# teensyShield3.net
KiCad netlist of a schematic drawn in EAGLE
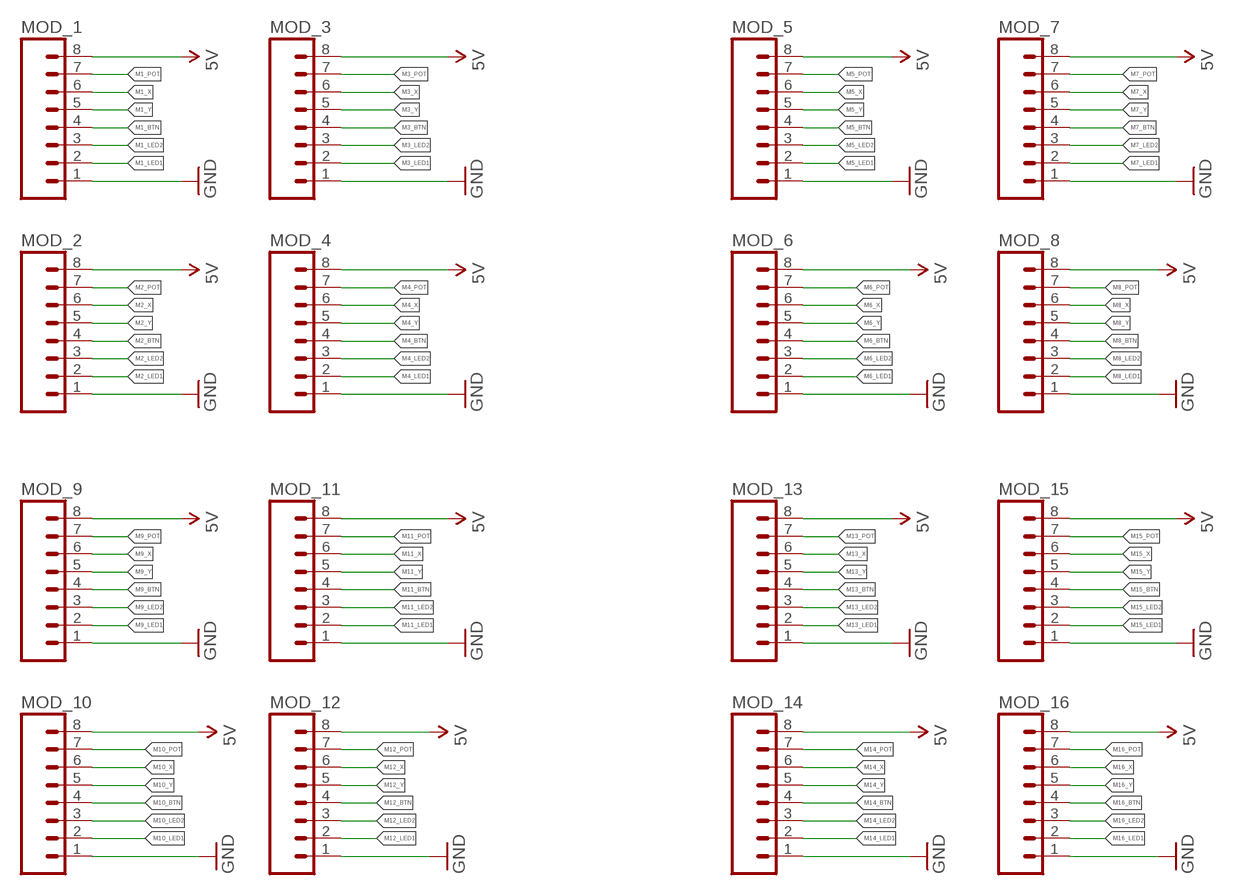
[diagram p0: schematic, sheet 1]

(export (version "E")
  (design (tool "Eeschema 10.0.6"))
  (components
    (comp (ref "MOD_1")
      (value "M08")
      (footprint "eagle-import:1X08_ROUND")
      (libsource (lib "eagle-import") (part "M08"))
    )
    (comp (ref "MOD_2")
      (value "M08")
      (footprint "eagle-import:1X08_ROUND")
      (libsource (lib "eagle-import") (part "M08"))
    )
    (comp (ref "MOD_3")
      (value "M08")
      (footprint "eagle-import:1X08_ROUND")
      (libsource (lib "eagle-import") (part "M08"))
    )
    (comp (ref "MOD_4")
      (value "M08")
      (footprint "eagle-import:1X08_ROUND")
      (libsource (lib "eagle-import") (part "M08"))
    )
    (comp (ref "MOD_5")
      (value "M08")
      (footprint "eagle-import:1X08_ROUND")
      (libsource (lib "eagle-import") (part "M08"))
    )
    (comp (ref "MOD_6")
      (value "M08")
      (footprint "eagle-import:1X08_ROUND")
      (libsource (lib "eagle-import") (part "M08"))
    )
    (comp (ref "MOD_7")
      (value "M08")
      (footprint "eagle-import:1X08_ROUND")
      (libsource (lib "eagle-import") (part "M08"))
    )
    (comp (ref "MOD_8")
      (value "M08")
      (footprint "eagle-import:1X08_ROUND")
      (libsource (lib "eagle-import") (part "M08"))
    )
    (comp (ref "MOD_9")
      (value "M08")
      (footprint "eagle-import:1X08_ROUND")
      (libsource (lib "eagle-import") (part "M08"))
    )
    (comp (ref "MOD_10")
      (value "M08")
      (footprint "eagle-import:1X08_ROUND")
      (libsource (lib "eagle-import") (part "M08"))
    )
    (comp (ref "MOD_11")
      (value "M08")
      (footprint "eagle-import:1X08_ROUND")
      (libsource (lib "eagle-import") (part "M08"))
    )
    (comp (ref "MOD_12")
      (value "M08")
      (footprint "eagle-import:1X08_ROUND")
      (libsource (lib "eagle-import") (part "M08"))
    )
    (comp (ref "MOD_13")
      (value "M08")
      (footprint "eagle-import:1X08_ROUND")
      (libsource (lib "eagle-import") (part "M08"))
    )
    (comp (ref "MOD_14")
      (value "M08")
      (footprint "eagle-import:1X08_ROUND")
      (libsource (lib "eagle-import") (part "M08"))
    )
    (comp (ref "MOD_15")
      (value "M08")
      (footprint "eagle-import:1X08_ROUND")
      (libsource (lib "eagle-import") (part "M08"))
    )
    (comp (ref "MOD_16")
      (value "M08")
      (footprint "eagle-import:1X08_ROUND")
      (libsource (lib "eagle-import") (part "M08"))
    )
  )
  (nets
    (net (code "1") (name "5V") (class "Default")
      (node (ref "MOD_1") (pin "8") (pinfunction "8_8") (pintype "passive"))
      (node (ref "MOD_10") (pin "8") (pinfunction "8_8") (pintype "passive"))
      (node (ref "MOD_11") (pin "8") (pinfunction "8_8") (pintype "passive"))
      (node (ref "MOD_12") (pin "8") (pinfunction "8_8") (pintype "passive"))
      (node (ref "MOD_13") (pin "8") (pinfunction "8_8") (pintype "passive"))
      (node (ref "MOD_14") (pin "8") (pinfunction "8_8") (pintype "passive"))
      (node (ref "MOD_15") (pin "8") (pinfunction "8_8") (pintype "passive"))
      (node (ref "MOD_16") (pin "8") (pinfunction "8_8") (pintype "passive"))
      (node (ref "MOD_2") (pin "8") (pinfunction "8_8") (pintype "passive"))
      (node (ref "MOD_3") (pin "8") (pinfunction "8_8") (pintype "passive"))
      (node (ref "MOD_4") (pin "8") (pinfunction "8_8") (pintype "passive"))
      (node (ref "MOD_5") (pin "8") (pinfunction "8_8") (pintype "passive"))
      (node (ref "MOD_6") (pin "8") (pinfunction "8_8") (pintype "passive"))
      (node (ref "MOD_7") (pin "8") (pinfunction "8_8") (pintype "passive"))
      (node (ref "MOD_8") (pin "8") (pinfunction "8_8") (pintype "passive"))
      (node (ref "MOD_9") (pin "8") (pinfunction "8_8") (pintype "passive"))
    )
    (net (code "2") (name "GND") (class "Default")
      (node (ref "MOD_1") (pin "1") (pinfunction "1_1") (pintype "passive"))
      (node (ref "MOD_10") (pin "1") (pinfunction "1_1") (pintype "passive"))
      (node (ref "MOD_11") (pin "1") (pinfunction "1_1") (pintype "passive"))
      (node (ref "MOD_12") (pin "1") (pinfunction "1_1") (pintype "passive"))
      (node (ref "MOD_13") (pin "1") (pinfunction "1_1") (pintype "passive"))
      (node (ref "MOD_14") (pin "1") (pinfunction "1_1") (pintype "passive"))
      (node (ref "MOD_15") (pin "1") (pinfunction "1_1") (pintype "passive"))
      (node (ref "MOD_16") (pin "1") (pinfunction "1_1") (pintype "passive"))
      (node (ref "MOD_2") (pin "1") (pinfunction "1_1") (pintype "passive"))
      (node (ref "MOD_3") (pin "1") (pinfunction "1_1") (pintype "passive"))
      (node (ref "MOD_4") (pin "1") (pinfunction "1_1") (pintype "passive"))
      (node (ref "MOD_5") (pin "1") (pinfunction "1_1") (pintype "passive"))
      (node (ref "MOD_6") (pin "1") (pinfunction "1_1") (pintype "passive"))
      (node (ref "MOD_7") (pin "1") (pinfunction "1_1") (pintype "passive"))
      (node (ref "MOD_8") (pin "1") (pinfunction "1_1") (pintype "passive"))
      (node (ref "MOD_9") (pin "1") (pinfunction "1_1") (pintype "passive"))
    )
    (net (code "3") (name "M1_BTN") (class "Default")
      (node (ref "MOD_1") (pin "4") (pinfunction "4_4") (pintype "passive"))
    )
    (net (code "4") (name "M1_LED1") (class "Default")
      (node (ref "MOD_1") (pin "2") (pinfunction "2_2") (pintype "passive"))
    )
    (net (code "5") (name "M1_LED2") (class "Default")
      (node (ref "MOD_1") (pin "3") (pinfunction "3_3") (pintype "passive"))
    )
    (net (code "6") (name "M1_POT") (class "Default")
      (node (ref "MOD_1") (pin "7") (pinfunction "7_7") (pintype "passive"))
    )
    (net (code "7") (name "M1_X") (class "Default")
      (node (ref "MOD_1") (pin "6") (pinfunction "6_6") (pintype "passive"))
    )
    (net (code "8") (name "M1_Y") (class "Default")
      (node (ref "MOD_1") (pin "5") (pinfunction "5_5") (pintype "passive"))
    )
    (net (code "9") (name "M2_BTN") (class "Default")
      (node (ref "MOD_2") (pin "4") (pinfunction "4_4") (pintype "passive"))
    )
    (net (code "10") (name "M2_LED1") (class "Default")
      (node (ref "MOD_2") (pin "2") (pinfunction "2_2") (pintype "passive"))
    )
    (net (code "11") (name "M2_LED2") (class "Default")
      (node (ref "MOD_2") (pin "3") (pinfunction "3_3") (pintype "passive"))
    )
    (net (code "12") (name "M2_POT") (class "Default")
      (node (ref "MOD_2") (pin "7") (pinfunction "7_7") (pintype "passive"))
    )
    (net (code "13") (name "M2_X") (class "Default")
      (node (ref "MOD_2") (pin "6") (pinfunction "6_6") (pintype "passive"))
    )
    (net (code "14") (name "M2_Y") (class "Default")
      (node (ref "MOD_2") (pin "5") (pinfunction "5_5") (pintype "passive"))
    )
    (net (code "15") (name "M3_BTN") (class "Default")
      (node (ref "MOD_3") (pin "4") (pinfunction "4_4") (pintype "passive"))
    )
    (net (code "16") (name "M3_LED1") (class "Default")
      (node (ref "MOD_3") (pin "2") (pinfunction "2_2") (pintype "passive"))
    )
    (net (code "17") (name "M3_LED2") (class "Default")
      (node (ref "MOD_3") (pin "3") (pinfunction "3_3") (pintype "passive"))
    )
    (net (code "18") (name "M3_POT") (class "Default")
      (node (ref "MOD_3") (pin "7") (pinfunction "7_7") (pintype "passive"))
    )
    (net (code "19") (name "M3_X") (class "Default")
      (node (ref "MOD_3") (pin "6") (pinfunction "6_6") (pintype "passive"))
    )
    (net (code "20") (name "M3_Y") (class "Default")
      (node (ref "MOD_3") (pin "5") (pinfunction "5_5") (pintype "passive"))
    )
    (net (code "21") (name "M4_BTN") (class "Default")
      (node (ref "MOD_4") (pin "4") (pinfunction "4_4") (pintype "passive"))
    )
    (net (code "22") (name "M4_LED1") (class "Default")
      (node (ref "MOD_4") (pin "2") (pinfunction "2_2") (pintype "passive"))
    )
    (net (code "23") (name "M4_LED2") (class "Default")
      (node (ref "MOD_4") (pin "3") (pinfunction "3_3") (pintype "passive"))
    )
    (net (code "24") (name "M4_POT") (class "Default")
      (node (ref "MOD_4") (pin "7") (pinfunction "7_7") (pintype "passive"))
    )
    (net (code "25") (name "M4_X") (class "Default")
      (node (ref "MOD_4") (pin "6") (pinfunction "6_6") (pintype "passive"))
    )
    (net (code "26") (name "M4_Y") (class "Default")
      (node (ref "MOD_4") (pin "5") (pinfunction "5_5") (pintype "passive"))
    )
    (net (code "27") (name "M5_BTN") (class "Default")
      (node (ref "MOD_5") (pin "4") (pinfunction "4_4") (pintype "passive"))
    )
    (net (code "28") (name "M5_LED1") (class "Default")
      (node (ref "MOD_5") (pin "2") (pinfunction "2_2") (pintype "passive"))
    )
    (net (code "29") (name "M5_LED2") (class "Default")
      (node (ref "MOD_5") (pin "3") (pinfunction "3_3") (pintype "passive"))
    )
    (net (code "30") (name "M5_POT") (class "Default")
      (node (ref "MOD_5") (pin "7") (pinfunction "7_7") (pintype "passive"))
    )
    (net (code "31") (name "M5_X") (class "Default")
      (node (ref "MOD_5") (pin "6") (pinfunction "6_6") (pintype "passive"))
    )
    (net (code "32") (name "M5_Y") (class "Default")
      (node (ref "MOD_5") (pin "5") (pinfunction "5_5") (pintype "passive"))
    )
    (net (code "33") (name "M6_BTN") (class "Default")
      (node (ref "MOD_6") (pin "4") (pinfunction "4_4") (pintype "passive"))
    )
    (net (code "34") (name "M6_LED1") (class "Default")
      (node (ref "MOD_6") (pin "2") (pinfunction "2_2") (pintype "passive"))
    )
    (net (code "35") (name "M6_LED2") (class "Default")
      (node (ref "MOD_6") (pin "3") (pinfunction "3_3") (pintype "passive"))
    )
    (net (code "36") (name "M6_POT") (class "Default")
      (node (ref "MOD_6") (pin "7") (pinfunction "7_7") (pintype "passive"))
    )
    (net (code "37") (name "M6_X") (class "Default")
      (node (ref "MOD_6") (pin "6") (pinfunction "6_6") (pintype "passive"))
    )
    (net (code "38") (name "M6_Y") (class "Default")
      (node (ref "MOD_6") (pin "5") (pinfunction "5_5") (pintype "passive"))
    )
    (net (code "39") (name "M7_BTN") (class "Default")
      (node (ref "MOD_7") (pin "4") (pinfunction "4_4") (pintype "passive"))
    )
    (net (code "40") (name "M7_LED1") (class "Default")
      (node (ref "MOD_7") (pin "2") (pinfunction "2_2") (pintype "passive"))
    )
    (net (code "41") (name "M7_LED2") (class "Default")
      (node (ref "MOD_7") (pin "3") (pinfunction "3_3") (pintype "passive"))
    )
    (net (code "42") (name "M7_POT") (class "Default")
      (node (ref "MOD_7") (pin "7") (pinfunction "7_7") (pintype "passive"))
    )
    (net (code "43") (name "M7_X") (class "Default")
      (node (ref "MOD_7") (pin "6") (pinfunction "6_6") (pintype "passive"))
    )
    (net (code "44") (name "M7_Y") (class "Default")
      (node (ref "MOD_7") (pin "5") (pinfunction "5_5") (pintype "passive"))
    )
    (net (code "45") (name "M8_BTN") (class "Default")
      (node (ref "MOD_8") (pin "4") (pinfunction "4_4") (pintype "passive"))
    )
    (net (code "46") (name "M8_LED1") (class "Default")
      (node (ref "MOD_8") (pin "2") (pinfunction "2_2") (pintype "passive"))
    )
    (net (code "47") (name "M8_LED2") (class "Default")
      (node (ref "MOD_8") (pin "3") (pinfunction "3_3") (pintype "passive"))
    )
    (net (code "48") (name "M8_POT") (class "Default")
      (node (ref "MOD_8") (pin "7") (pinfunction "7_7") (pintype "passive"))
    )
    (net (code "49") (name "M8_X") (class "Default")
      (node (ref "MOD_8") (pin "6") (pinfunction "6_6") (pintype "passive"))
    )
    (net (code "50") (name "M8_Y") (class "Default")
      (node (ref "MOD_8") (pin "5") (pinfunction "5_5") (pintype "passive"))
    )
    (net (code "51") (name "M9_BTN") (class "Default")
      (node (ref "MOD_9") (pin "4") (pinfunction "4_4") (pintype "passive"))
    )
    (net (code "52") (name "M9_LED1") (class "Default")
      (node (ref "MOD_9") (pin "2") (pinfunction "2_2") (pintype "passive"))
    )
    (net (code "53") (name "M9_LED2") (class "Default")
      (node (ref "MOD_9") (pin "3") (pinfunction "3_3") (pintype "passive"))
    )
    (net (code "54") (name "M9_POT") (class "Default")
      (node (ref "MOD_9") (pin "7") (pinfunction "7_7") (pintype "passive"))
    )
    (net (code "55") (name "M9_X") (class "Default")
      (node (ref "MOD_9") (pin "6") (pinfunction "6_6") (pintype "passive"))
    )
    (net (code "56") (name "M9_Y") (class "Default")
      (node (ref "MOD_9") (pin "5") (pinfunction "5_5") (pintype "passive"))
    )
    (net (code "57") (name "M10_BTN") (class "Default")
      (node (ref "MOD_10") (pin "4") (pinfunction "4_4") (pintype "passive"))
    )
    (net (code "58") (name "M10_LED1") (class "Default")
      (node (ref "MOD_10") (pin "2") (pinfunction "2_2") (pintype "passive"))
    )
    (net (code "59") (name "M10_LED2") (class "Default")
      (node (ref "MOD_10") (pin "3") (pinfunction "3_3") (pintype "passive"))
    )
    (net (code "60") (name "M10_POT") (class "Default")
      (node (ref "MOD_10") (pin "7") (pinfunction "7_7") (pintype "passive"))
    )
    (net (code "61") (name "M10_X") (class "Default")
      (node (ref "MOD_10") (pin "6") (pinfunction "6_6") (pintype "passive"))
    )
    (net (code "62") (name "M10_Y") (class "Default")
      (node (ref "MOD_10") (pin "5") (pinfunction "5_5") (pintype "passive"))
    )
    (net (code "63") (name "M11_BTN") (class "Default")
      (node (ref "MOD_11") (pin "4") (pinfunction "4_4") (pintype "passive"))
    )
    (net (code "64") (name "M11_LED1") (class "Default")
      (node (ref "MOD_11") (pin "2") (pinfunction "2_2") (pintype "passive"))
    )
    (net (code "65") (name "M11_LED2") (class "Default")
      (node (ref "MOD_11") (pin "3") (pinfunction "3_3") (pintype "passive"))
    )
    (net (code "66") (name "M11_POT") (class "Default")
      (node (ref "MOD_11") (pin "7") (pinfunction "7_7") (pintype "passive"))
    )
    (net (code "67") (name "M11_X") (class "Default")
      (node (ref "MOD_11") (pin "6") (pinfunction "6_6") (pintype "passive"))
    )
    (net (code "68") (name "M11_Y") (class "Default")
      (node (ref "MOD_11") (pin "5") (pinfunction "5_5") (pintype "passive"))
    )
    (net (code "69") (name "M12_BTN") (class "Default")
      (node (ref "MOD_12") (pin "4") (pinfunction "4_4") (pintype "passive"))
    )
    (net (code "70") (name "M12_LED1") (class "Default")
      (node (ref "MOD_12") (pin "2") (pinfunction "2_2") (pintype "passive"))
    )
    (net (code "71") (name "M12_LED2") (class "Default")
      (node (ref "MOD_12") (pin "3") (pinfunction "3_3") (pintype "passive"))
    )
    (net (code "72") (name "M12_POT") (class "Default")
      (node (ref "MOD_12") (pin "7") (pinfunction "7_7") (pintype "passive"))
    )
    (net (code "73") (name "M12_X") (class "Default")
      (node (ref "MOD_12") (pin "6") (pinfunction "6_6") (pintype "passive"))
    )
    (net (code "74") (name "M12_Y") (class "Default")
      (node (ref "MOD_12") (pin "5") (pinfunction "5_5") (pintype "passive"))
    )
    (net (code "75") (name "M13_BTN") (class "Default")
      (node (ref "MOD_13") (pin "4") (pinfunction "4_4") (pintype "passive"))
    )
    (net (code "76") (name "M13_LED1") (class "Default")
      (node (ref "MOD_13") (pin "2") (pinfunction "2_2") (pintype "passive"))
    )
    (net (code "77") (name "M13_LED2") (class "Default")
      (node (ref "MOD_13") (pin "3") (pinfunction "3_3") (pintype "passive"))
    )
    (net (code "78") (name "M13_POT") (class "Default")
      (node (ref "MOD_13") (pin "7") (pinfunction "7_7") (pintype "passive"))
    )
    (net (code "79") (name "M13_X") (class "Default")
      (node (ref "MOD_13") (pin "6") (pinfunction "6_6") (pintype "passive"))
    )
    (net (code "80") (name "M13_Y") (class "Default")
      (node (ref "MOD_13") (pin "5") (pinfunction "5_5") (pintype "passive"))
    )
    (net (code "81") (name "M14_BTN") (class "Default")
      (node (ref "MOD_14") (pin "4") (pinfunction "4_4") (pintype "passive"))
    )
    (net (code "82") (name "M14_LED1") (class "Default")
      (node (ref "MOD_14") (pin "2") (pinfunction "2_2") (pintype "passive"))
    )
    (net (code "83") (name "M14_LED2") (class "Default")
      (node (ref "MOD_14") (pin "3") (pinfunction "3_3") (pintype "passive"))
    )
    (net (code "84") (name "M14_POT") (class "Default")
      (node (ref "MOD_14") (pin "7") (pinfunction "7_7") (pintype "passive"))
    )
    (net (code "85") (name "M14_X") (class "Default")
      (node (ref "MOD_14") (pin "6") (pinfunction "6_6") (pintype "passive"))
    )
    (net (code "86") (name "M14_Y") (class "Default")
      (node (ref "MOD_14") (pin "5") (pinfunction "5_5") (pintype "passive"))
    )
    (net (code "87") (name "M15_BTN") (class "Default")
      (node (ref "MOD_15") (pin "4") (pinfunction "4_4") (pintype "passive"))
    )
    (net (code "88") (name "M15_LED1") (class "Default")
      (node (ref "MOD_15") (pin "2") (pinfunction "2_2") (pintype "passive"))
    )
    (net (code "89") (name "M15_LED2") (class "Default")
      (node (ref "MOD_15") (pin "3") (pinfunction "3_3") (pintype "passive"))
    )
    (net (code "90") (name "M15_POT") (class "Default")
      (node (ref "MOD_15") (pin "7") (pinfunction "7_7") (pintype "passive"))
    )
    (net (code "91") (name "M15_X") (class "Default")
      (node (ref "MOD_15") (pin "6") (pinfunction "6_6") (pintype "passive"))
    )
    (net (code "92") (name "M15_Y") (class "Default")
      (node (ref "MOD_15") (pin "5") (pinfunction "5_5") (pintype "passive"))
    )
    (net (code "93") (name "M16_BTN") (class "Default")
      (node (ref "MOD_16") (pin "4") (pinfunction "4_4") (pintype "passive"))
    )
    (net (code "94") (name "M16_LED1") (class "Default")
      (node (ref "MOD_16") (pin "2") (pinfunction "2_2") (pintype "passive"))
    )
    (net (code "95") (name "M16_LED2") (class "Default")
      (node (ref "MOD_16") (pin "3") (pinfunction "3_3") (pintype "passive"))
    )
    (net (code "96") (name "M16_POT") (class "Default")
      (node (ref "MOD_16") (pin "7") (pinfunction "7_7") (pintype "passive"))
    )
    (net (code "97") (name "M16_X") (class "Default")
      (node (ref "MOD_16") (pin "6") (pinfunction "6_6") (pintype "passive"))
    )
    (net (code "98") (name "M16_Y") (class "Default")
      (node (ref "MOD_16") (pin "5") (pinfunction "5_5") (pintype "passive"))
    )
  )
)
